# SSB_Transceiver_Supply_PCB.net
KiCad netlist of a schematic drawn in EAGLE
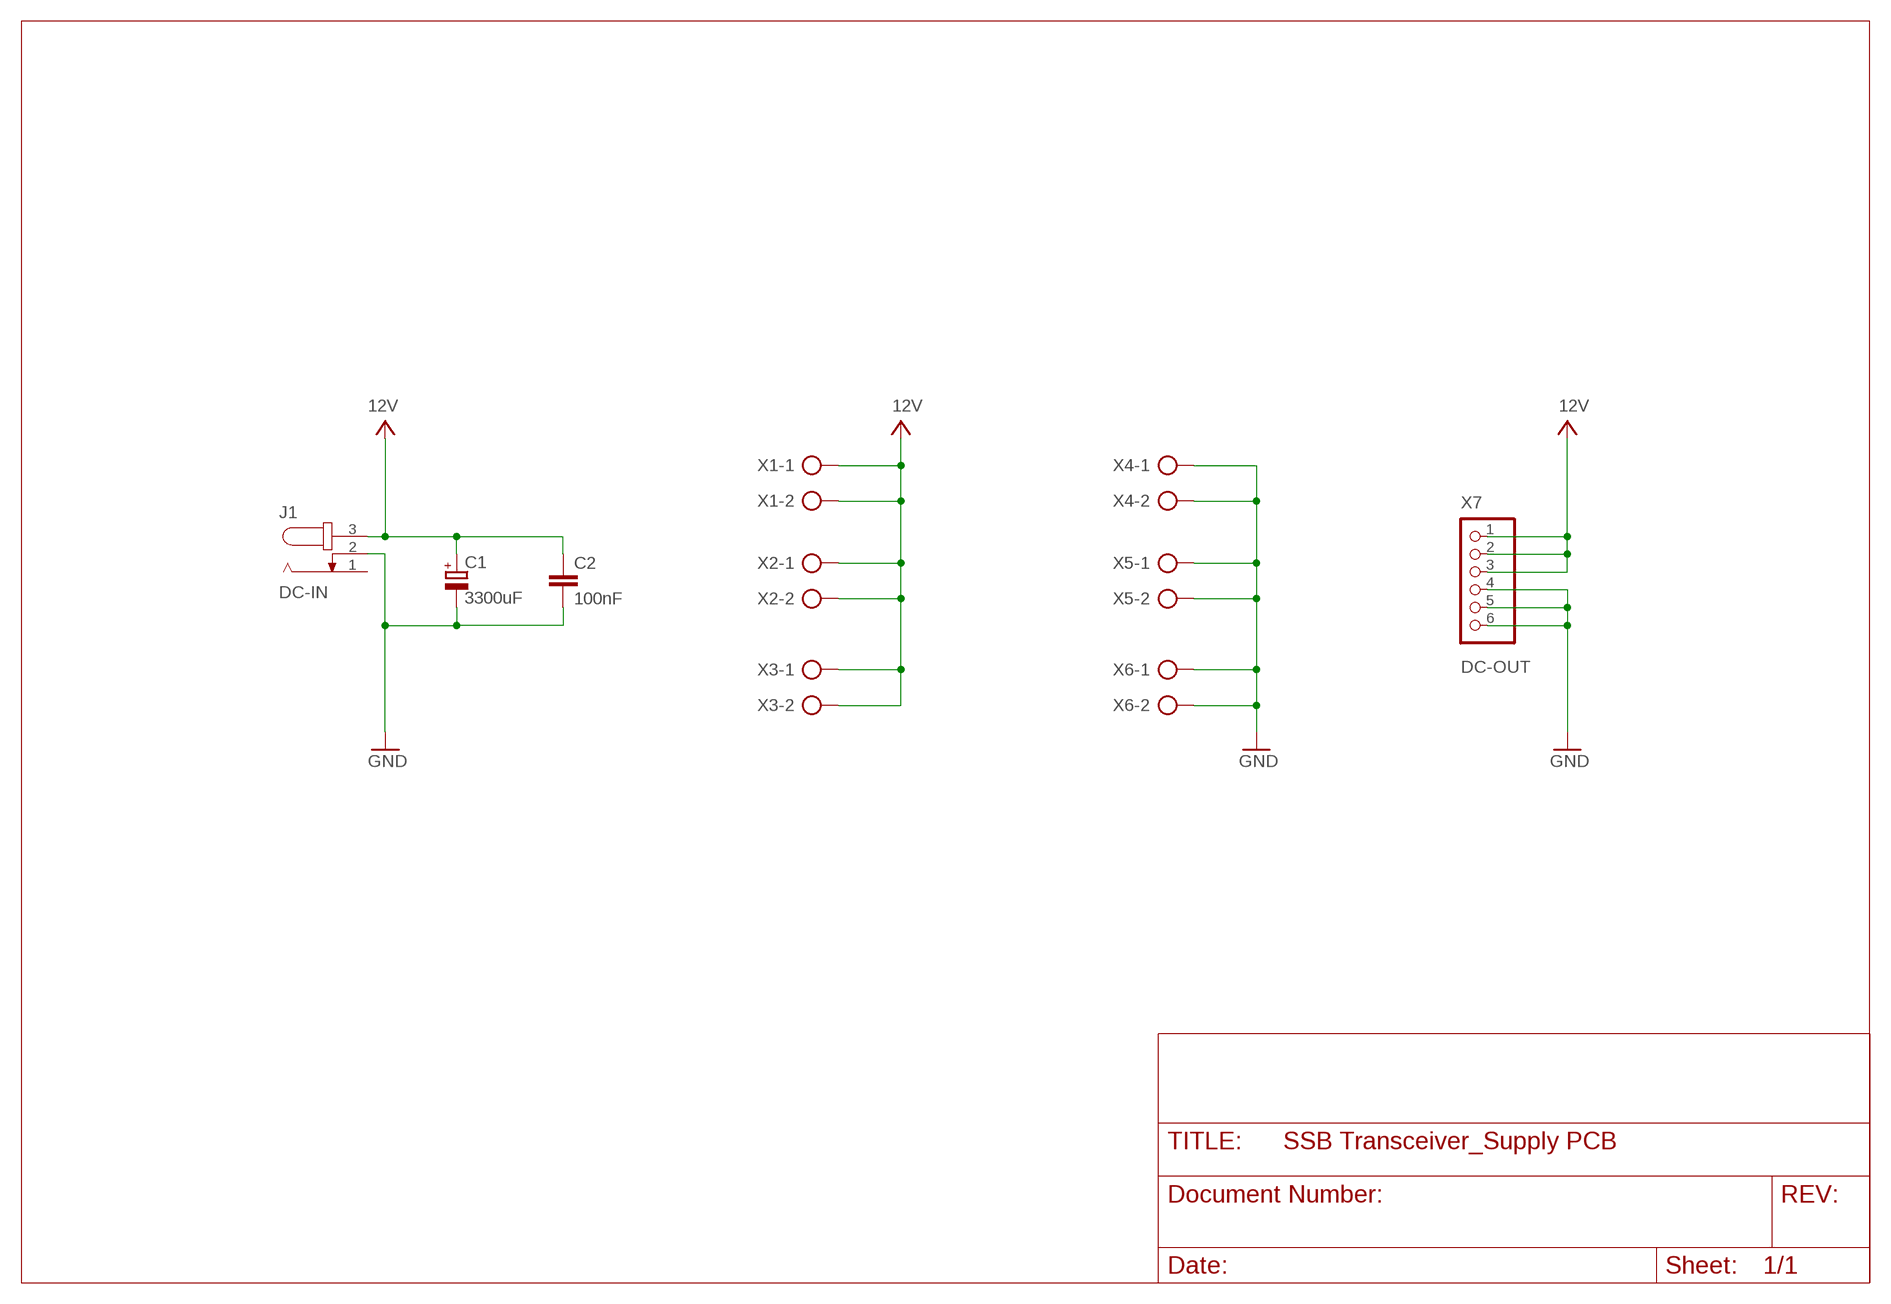
[diagram p0: schematic, sheet 1]

(export (version "E")
  (design (tool "Eeschema 10.0.6"))
  (components
    (comp (ref "C1")
      (value "3300uF")
      (footprint "eagle-import:E7,5-16")
      (libsource (lib "eagle-import") (part "CPOL-EUE7.5-16"))
    )
    (comp (ref "C2")
      (value "100nF")
      (footprint "eagle-import:C0805K")
      (libsource (lib "eagle-import") (part "C-EUC0805K"))
    )
    (comp (ref "J1")
      (value "DC-IN")
      (footprint "eagle-import:SPC4078")
      (libsource (lib "eagle-import") (part "JACK-PLUG1"))
    )
    (comp (ref "X1")
      (value "12V")
      (footprint "eagle-import:AK300_2")
      (libsource (lib "eagle-import") (part "AK300/2"))
    )
    (comp (ref "X2")
      (value "AK300/2")
      (footprint "eagle-import:AK300_2")
      (libsource (lib "eagle-import") (part "AK300/2"))
    )
    (comp (ref "X3")
      (value "AK300/2")
      (footprint "eagle-import:AK300_2")
      (libsource (lib "eagle-import") (part "AK300/2"))
    )
    (comp (ref "X4")
      (value "AK300/2")
      (footprint "eagle-import:AK300_2")
      (libsource (lib "eagle-import") (part "AK300/2"))
    )
    (comp (ref "X5")
      (value "AK300/2")
      (footprint "eagle-import:AK300_2")
      (libsource (lib "eagle-import") (part "AK300/2"))
    )
    (comp (ref "X6")
      (value "AK300/2")
      (footprint "eagle-import:AK300_2")
      (libsource (lib "eagle-import") (part "AK300/2"))
    )
    (comp (ref "X7")
      (value "DC-OUT")
      (footprint "eagle-import:1X06")
      (libsource (lib "eagle-import") (part "PINHD-1X6"))
    )
  )
  (nets
    (net (code "1") (name "12V") (class "Default")
      (node (ref "C1") (pin "+") (pinfunction "+_+") (pintype "passive"))
      (node (ref "C2") (pin "1") (pinfunction "1_1") (pintype "passive"))
      (node (ref "J1") (pin "3") (pinfunction "3_3") (pintype "passive"))
      (node (ref "X1") (pin "1") (pinfunction "KL_1") (pintype "passive"))
      (node (ref "X1") (pin "2") (pinfunction "KL_2") (pintype "passive"))
      (node (ref "X2") (pin "1") (pinfunction "KL_1") (pintype "passive"))
      (node (ref "X2") (pin "2") (pinfunction "KL_2") (pintype "passive"))
      (node (ref "X3") (pin "1") (pinfunction "KL_1") (pintype "passive"))
      (node (ref "X3") (pin "2") (pinfunction "KL_2") (pintype "passive"))
      (node (ref "X7") (pin "1") (pinfunction "1_1") (pintype "passive"))
      (node (ref "X7") (pin "2") (pinfunction "2_2") (pintype "passive"))
      (node (ref "X7") (pin "3") (pinfunction "3_3") (pintype "passive"))
    )
    (net (code "2") (name "GND") (class "Default")
      (node (ref "C1") (pin "-") (pinfunction "-_-") (pintype "passive"))
      (node (ref "C2") (pin "2") (pinfunction "2_2") (pintype "passive"))
      (node (ref "J1") (pin "2") (pinfunction "2_2") (pintype "passive"))
      (node (ref "X4") (pin "1") (pinfunction "KL_1") (pintype "passive"))
      (node (ref "X4") (pin "2") (pinfunction "KL_2") (pintype "passive"))
      (node (ref "X5") (pin "1") (pinfunction "KL_1") (pintype "passive"))
      (node (ref "X5") (pin "2") (pinfunction "KL_2") (pintype "passive"))
      (node (ref "X6") (pin "1") (pinfunction "KL_1") (pintype "passive"))
      (node (ref "X6") (pin "2") (pinfunction "KL_2") (pintype "passive"))
      (node (ref "X7") (pin "4") (pinfunction "4_4") (pintype "passive"))
      (node (ref "X7") (pin "5") (pinfunction "5_5") (pintype "passive"))
      (node (ref "X7") (pin "6") (pinfunction "6_6") (pintype "passive"))
    )
    (net (code "3") (name "unconnected-(J1-Pad1)") (class "Default")
      (node (ref "J1") (pin "1") (pinfunction "1_1") (pintype "passive"))
    )
  )
)
